# Sensors.net
KiCad netlist of a schematic drawn in Altium Designer
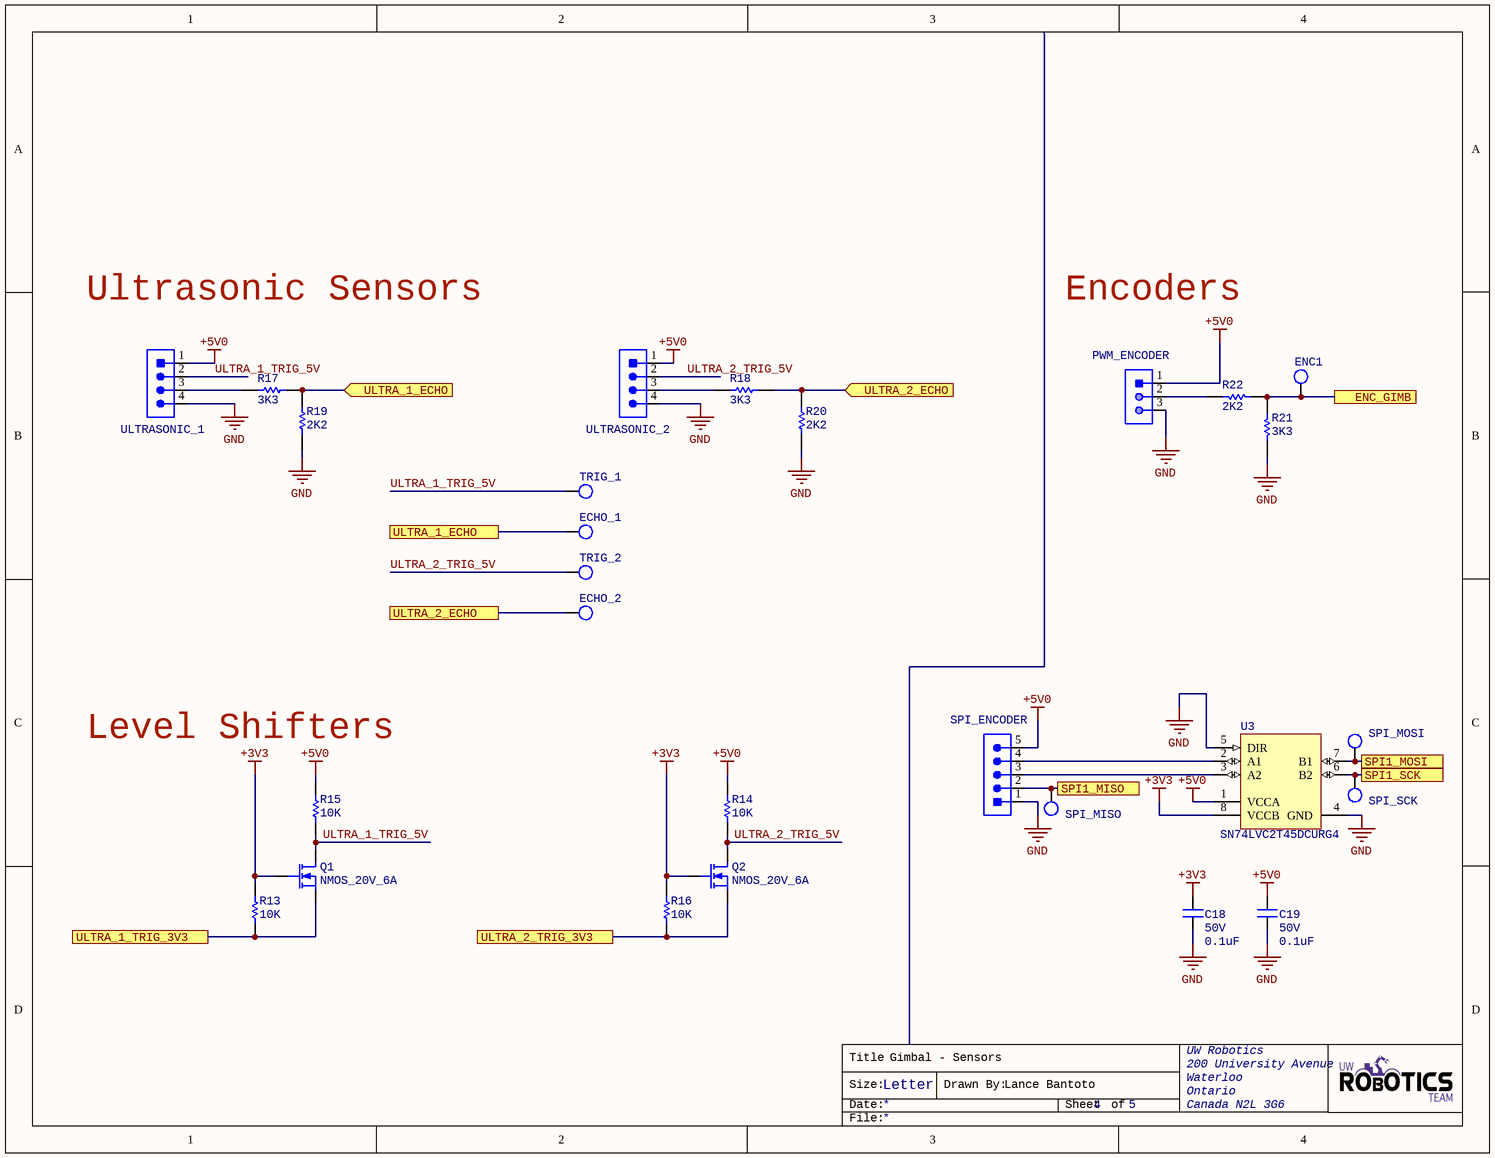
[diagram p0: Sensors.SchDoc]

(export (version "E")
  (design (tool "Eeschema 10.0.6"))
  (components
    (comp (ref "C18")
      (value "0.1uF")
      (footprint "CAPC0603(1608)55_N")
      (description "CAP CER 0.1UF 50V X7R 0603")
      (fields
        (field (name "MPN") "CC0603KRX7R9BB104")
        (field (name "MANUFACTURER") "Yageo")
        (field (name "VOLTAGE RATING") "50V")
      )
      (libsource (lib "UWRT_Schematic_Library_2020") (part "CAP_0.1uF_50V_0603"))
    )
    (comp (ref "C19")
      (value "0.1uF")
      (footprint "CAPC0603(1608)55_N")
      (description "CAP CER 0.1UF 50V X7R 0603")
      (fields
        (field (name "MPN") "CC0603KRX7R9BB104")
        (field (name "MANUFACTURER") "Yageo")
        (field (name "VOLTAGE RATING") "50V")
      )
      (libsource (lib "UWRT_Schematic_Library_2020") (part "CAP_0.1uF_50V_0603"))
    )
    (comp (ref "ECHO_1")
      (value "TESTPOINT_LOOP")
      (footprint "TESTPOINT_LOOP")
      (description "Loop testpoint through-hole pad")
      (fields (field (name "MANUFACTURER") "Keystone Electronics"))
      (libsource (lib "UWRT_Schematic_Library_2020") (part "TESTPOINT_LOOP"))
    )
    (comp (ref "ECHO_2")
      (value "TESTPOINT_LOOP")
      (footprint "TESTPOINT_LOOP")
      (description "Loop testpoint through-hole pad")
      (fields (field (name "MANUFACTURER") "Keystone Electronics"))
      (libsource (lib "UWRT_Schematic_Library_2020") (part "TESTPOINT_LOOP"))
    )
    (comp (ref "ENC1")
      (value "TESTPOINT_LOOP")
      (footprint "TESTPOINT_LOOP")
      (description "Loop testpoint through-hole pad")
      (fields (field (name "MANUFACTURER") "Keystone Electronics"))
      (libsource (lib "UWRT_Schematic_Library_2020") (part "TESTPOINT_LOOP"))
    )
    (comp (ref "PWM_ENCODER")
      (value "CON_3M_SM4")
      (footprint "JST-B3B-SM4-TB")
      (fields
        (field (name "MANUFACTURER") "JST")
        (field (name "MANUFACTURER PART NUMBER") "B3B-PH-SM4-TB(LF)(SN)")
      )
      (libsource (lib "UWRT_Schematic_Library_2020") (part "CON_3M_SM4"))
    )
    (comp (ref "Q1")
      (value "NMOS_20V_6A")
      (footprint "NMOS_SOT23-3")
      (description "MOSFET N-CH 20V 6A SOT23")
      (fields (field (name "MPN") "AO3420") (field (name "MANUFACTURER") "Alpha & Omega"))
      (libsource (lib "UWRT_Schematic_Library_2020") (part "NMOS_20V_6A"))
    )
    (comp (ref "Q2")
      (value "NMOS_20V_6A")
      (footprint "NMOS_SOT23-3")
      (description "MOSFET N-CH 20V 6A SOT23")
      (fields (field (name "MPN") "AO3420") (field (name "MANUFACTURER") "Alpha & Omega"))
      (libsource (lib "UWRT_Schematic_Library_2020") (part "NMOS_20V_6A"))
    )
    (comp (ref "R13")
      (value "10K")
      (footprint "RESC0603(1608)_N")
      (description "RES SMD 10K OHM 5% 1/10W 0603")
      (fields (field (name "MANUFACTURER") "Yageo") (field (name "MPN") "RC0603JR-0710KL"))
      (libsource (lib "UWRT_Schematic_Library_2020") (part "RES_10K_0603"))
    )
    (comp (ref "R14")
      (value "10K")
      (footprint "RESC0603(1608)_N")
      (description "RES SMD 10K OHM 5% 1/10W 0603")
      (fields (field (name "MANUFACTURER") "Yageo") (field (name "MPN") "RC0603JR-0710KL"))
      (libsource (lib "UWRT_Schematic_Library_2020") (part "RES_10K_0603"))
    )
    (comp (ref "R15")
      (value "10K")
      (footprint "RESC0603(1608)_N")
      (description "RES SMD 10K OHM 5% 1/10W 0603")
      (fields (field (name "MANUFACTURER") "Yageo") (field (name "MPN") "RC0603JR-0710KL"))
      (libsource (lib "UWRT_Schematic_Library_2020") (part "RES_10K_0603"))
    )
    (comp (ref "R16")
      (value "10K")
      (footprint "RESC0603(1608)_N")
      (description "RES SMD 10K OHM 5% 1/10W 0603")
      (fields (field (name "MANUFACTURER") "Yageo") (field (name "MPN") "RC0603JR-0710KL"))
      (libsource (lib "UWRT_Schematic_Library_2020") (part "RES_10K_0603"))
    )
    (comp (ref "R17")
      (value "3K3")
      (footprint "RESC0603(1608)_N")
      (description "RES SMD 3.3K OHM 5% 1/10W 0603")
      (fields (field (name "MANUFACTURER") "Yageo") (field (name "TOLERANCE") "5%"))
      (libsource (lib "UWRT_Schematic_Library_2020") (part "RES_3K3_0603"))
    )
    (comp (ref "R18")
      (value "3K3")
      (footprint "RESC0603(1608)_N")
      (description "RES SMD 3.3K OHM 5% 1/10W 0603")
      (fields (field (name "MANUFACTURER") "Yageo") (field (name "TOLERANCE") "5%"))
      (libsource (lib "UWRT_Schematic_Library_2020") (part "RES_3K3_0603"))
    )
    (comp (ref "R19")
      (value "2K2")
      (footprint "RESC0603(1608)_N")
      (description "RES SMD 2.2K OHM 1% 1/10W 0603")
      (fields (field (name "MANUFACTURER") "Yageo") (field (name "TOLERANCE") "1%"))
      (libsource (lib "UWRT_Schematic_Library_2020") (part "RES_2K2_0603"))
    )
    (comp (ref "R20")
      (value "2K2")
      (footprint "RESC0603(1608)_N")
      (description "RES SMD 2.2K OHM 1% 1/10W 0603")
      (fields (field (name "MANUFACTURER") "Yageo") (field (name "TOLERANCE") "1%"))
      (libsource (lib "UWRT_Schematic_Library_2020") (part "RES_2K2_0603"))
    )
    (comp (ref "R21")
      (value "3K3")
      (footprint "RESC0603(1608)_N")
      (description "RES SMD 3.3K OHM 5% 1/10W 0603")
      (fields (field (name "MANUFACTURER") "Yageo") (field (name "TOLERANCE") "5%"))
      (libsource (lib "UWRT_Schematic_Library_2020") (part "RES_3K3_0603"))
    )
    (comp (ref "R22")
      (value "2K2")
      (footprint "RESC0603(1608)_N")
      (description "RES SMD 2.2K OHM 1% 1/10W 0603")
      (fields (field (name "MANUFACTURER") "Yageo") (field (name "TOLERANCE") "1%"))
      (libsource (lib "UWRT_Schematic_Library_2020") (part "RES_2K2_0603"))
    )
    (comp (ref "SPI_ENCODER")
      (value "CON_5M_SM4")
      (footprint "JST-B5B-SM4-TB")
      (fields
        (field (name "MANUFACTURER") "JST")
        (field (name "MANUFACTURER PART NUMBER") "B5B-PH-SM4-TB(LF)(SN)")
      )
      (libsource (lib "UWRT_Schematic_Library_2020") (part "CON_5M_SM4"))
    )
    (comp (ref "SPI_MISO")
      (value "TESTPOINT_LOOP")
      (footprint "TESTPOINT_LOOP")
      (description "Loop testpoint through-hole pad")
      (fields (field (name "MANUFACTURER") "Keystone Electronics"))
      (libsource (lib "UWRT_Schematic_Library_2020") (part "TESTPOINT_LOOP"))
    )
    (comp (ref "SPI_MOSI")
      (value "TESTPOINT_LOOP")
      (footprint "TESTPOINT_LOOP")
      (description "Loop testpoint through-hole pad")
      (fields (field (name "MANUFACTURER") "Keystone Electronics"))
      (libsource (lib "UWRT_Schematic_Library_2020") (part "TESTPOINT_LOOP"))
    )
    (comp (ref "SPI_SCK")
      (value "TESTPOINT_LOOP")
      (footprint "TESTPOINT_LOOP")
      (description "Loop testpoint through-hole pad")
      (fields (field (name "MANUFACTURER") "Keystone Electronics"))
      (libsource (lib "UWRT_Schematic_Library_2020") (part "TESTPOINT_LOOP"))
    )
    (comp (ref "TRIG_1")
      (value "TESTPOINT_LOOP")
      (footprint "TESTPOINT_LOOP")
      (description "Loop testpoint through-hole pad")
      (fields (field (name "MANUFACTURER") "Keystone Electronics"))
      (libsource (lib "UWRT_Schematic_Library_2020") (part "TESTPOINT_LOOP"))
    )
    (comp (ref "TRIG_2")
      (value "TESTPOINT_LOOP")
      (footprint "TESTPOINT_LOOP")
      (description "Loop testpoint through-hole pad")
      (fields (field (name "MANUFACTURER") "Keystone Electronics"))
      (libsource (lib "UWRT_Schematic_Library_2020") (part "TESTPOINT_LOOP"))
    )
    (comp (ref "U3")
      (value "SN74LVC2T45DCURG4")
      (footprint "DCU0008A_L")
      (fields
        (field (name "MANUFACTURER") "Texas Instruments")
        (field (name "GENERIC PART NUMBER") "SN74LVC2T45")
      )
      (libsource (lib "Altium Content Vault") (part "TI-SN74XVC2T45-8"))
    )
    (comp (ref "ULTRASONIC_1")
      (value "CON_4M_SM4")
      (footprint "JST-B4B-SM4-TB")
      (fields
        (field (name "MANUFACTURER") "JST")
        (field (name "MANUFACTURER PART NUMBER") "B4B-PH-SM4-TB(LF)(SN)")
      )
      (libsource (lib "UWRT_Schematic_Library_2020") (part "CON_4M_SM4"))
    )
    (comp (ref "ULTRASONIC_2")
      (value "CON_4M_SM4")
      (footprint "JST-B4B-SM4-TB")
      (fields
        (field (name "MANUFACTURER") "JST")
        (field (name "MANUFACTURER PART NUMBER") "B4B-PH-SM4-TB(LF)(SN)")
      )
      (libsource (lib "UWRT_Schematic_Library_2020") (part "CON_4M_SM4"))
    )
  )
  (nets
    (net (code "1") (name "+3V3") (class "Default")
      (node (ref "C18") (pin "2") (pinfunction "2_2") (pintype "passive"))
      (node (ref "Q1") (pin "1") (pinfunction "G_1") (pintype "passive"))
      (node (ref "Q2") (pin "1") (pinfunction "G_1") (pintype "passive"))
      (node (ref "R13") (pin "1") (pinfunction "1_1") (pintype "passive"))
      (node (ref "R16") (pin "1") (pinfunction "1_1") (pintype "passive"))
      (node (ref "U3") (pin "8") (pinfunction "VCCB_8") (pintype "power_in"))
    )
    (net (code "2") (name "+5V0") (class "Default")
      (node (ref "C19") (pin "2") (pinfunction "2_2") (pintype "passive"))
      (node (ref "PWM_ENCODER") (pin "1") (pinfunction "1_1") (pintype "passive"))
      (node (ref "R14") (pin "2") (pinfunction "2_2") (pintype "passive"))
      (node (ref "R15") (pin "2") (pinfunction "2_2") (pintype "passive"))
      (node (ref "SPI_ENCODER") (pin "5") (pinfunction "5_5") (pintype "passive"))
      (node (ref "U3") (pin "1") (pinfunction "VCCA_1") (pintype "power_in"))
      (node (ref "ULTRASONIC_1") (pin "1") (pinfunction "1_1") (pintype "passive"))
      (node (ref "ULTRASONIC_2") (pin "1") (pinfunction "1_1") (pintype "passive"))
    )
    (net (code "3") (name "/ENC_GIMB") (class "Default")
      (node (ref "ENC1") (pin "1") (pintype "passive"))
      (node (ref "R21") (pin "1") (pinfunction "1_1") (pintype "passive"))
      (node (ref "R22") (pin "1") (pinfunction "1_1") (pintype "passive"))
    )
    (net (code "4") (name "/SPI1_MISO") (class "Default")
      (node (ref "SPI_ENCODER") (pin "2") (pinfunction "2_2") (pintype "passive"))
      (node (ref "SPI_MISO") (pin "1") (pintype "passive"))
    )
    (net (code "5") (name "/SPI1_MOSI") (class "Default")
      (node (ref "SPI_MOSI") (pin "1") (pintype "passive"))
      (node (ref "U3") (pin "7") (pinfunction "B1_7") (pintype "bidirectional"))
    )
    (net (code "6") (name "/SPI1_SCK") (class "Default")
      (node (ref "SPI_SCK") (pin "1") (pintype "passive"))
      (node (ref "U3") (pin "6") (pinfunction "B2_6") (pintype "bidirectional"))
    )
    (net (code "7") (name "/ULTRA_1_ECHO") (class "Default")
      (node (ref "ECHO_1") (pin "1") (pintype "passive"))
      (node (ref "R17") (pin "1") (pinfunction "1_1") (pintype "passive"))
      (node (ref "R19") (pin "2") (pinfunction "2_2") (pintype "passive"))
    )
    (net (code "8") (name "/ULTRA_1_TRIG_3V3") (class "Default")
      (node (ref "Q1") (pin "2") (pinfunction "S_2") (pintype "passive"))
      (node (ref "R13") (pin "2") (pinfunction "2_2") (pintype "passive"))
    )
    (net (code "9") (name "/ULTRA_1_TRIG_5V") (class "Default")
      (node (ref "Q1") (pin "3") (pinfunction "D_3") (pintype "passive"))
      (node (ref "R15") (pin "1") (pinfunction "1_1") (pintype "passive"))
      (node (ref "TRIG_1") (pin "1") (pintype "passive"))
      (node (ref "ULTRASONIC_1") (pin "2") (pinfunction "2_2") (pintype "passive"))
    )
    (net (code "10") (name "/ULTRA_2_ECHO") (class "Default")
      (node (ref "ECHO_2") (pin "1") (pintype "passive"))
      (node (ref "R18") (pin "1") (pinfunction "1_1") (pintype "passive"))
      (node (ref "R20") (pin "2") (pinfunction "2_2") (pintype "passive"))
    )
    (net (code "11") (name "/ULTRA_2_TRIG_3V3") (class "Default")
      (node (ref "Q2") (pin "2") (pinfunction "S_2") (pintype "passive"))
      (node (ref "R16") (pin "2") (pinfunction "2_2") (pintype "passive"))
    )
    (net (code "12") (name "/ULTRA_2_TRIG_5V") (class "Default")
      (node (ref "Q2") (pin "3") (pinfunction "D_3") (pintype "passive"))
      (node (ref "R14") (pin "1") (pinfunction "1_1") (pintype "passive"))
      (node (ref "TRIG_2") (pin "1") (pintype "passive"))
      (node (ref "ULTRASONIC_2") (pin "2") (pinfunction "2_2") (pintype "passive"))
    )
    (net (code "13") (name "GND") (class "Default")
      (node (ref "C18") (pin "1") (pinfunction "1_1") (pintype "passive"))
      (node (ref "C19") (pin "1") (pinfunction "1_1") (pintype "passive"))
      (node (ref "PWM_ENCODER") (pin "3") (pinfunction "3_3") (pintype "passive"))
      (node (ref "R19") (pin "1") (pinfunction "1_1") (pintype "passive"))
      (node (ref "R20") (pin "1") (pinfunction "1_1") (pintype "passive"))
      (node (ref "R21") (pin "2") (pinfunction "2_2") (pintype "passive"))
      (node (ref "SPI_ENCODER") (pin "1") (pinfunction "1_1") (pintype "passive"))
      (node (ref "U3") (pin "4") (pinfunction "GND_4") (pintype "power_in"))
      (node (ref "U3") (pin "5") (pinfunction "DIR_5") (pintype "input"))
      (node (ref "ULTRASONIC_1") (pin "4") (pinfunction "4_4") (pintype "passive"))
      (node (ref "ULTRASONIC_2") (pin "4") (pinfunction "4_4") (pintype "passive"))
    )
    (net (code "14") (name "Net-(PWM_ENCODER-Pad2)") (class "Default")
      (node (ref "PWM_ENCODER") (pin "2") (pinfunction "2_2") (pintype "passive"))
      (node (ref "R22") (pin "2") (pinfunction "2_2") (pintype "passive"))
    )
    (net (code "15") (name "Net-(R17-Pad2)") (class "Default")
      (node (ref "R17") (pin "2") (pinfunction "2_2") (pintype "passive"))
      (node (ref "ULTRASONIC_1") (pin "3") (pinfunction "3_3") (pintype "passive"))
    )
    (net (code "16") (name "Net-(R18-Pad2)") (class "Default")
      (node (ref "R18") (pin "2") (pinfunction "2_2") (pintype "passive"))
      (node (ref "ULTRASONIC_2") (pin "3") (pinfunction "3_3") (pintype "passive"))
    )
    (net (code "17") (name "Net-(U3-A1)") (class "Default")
      (node (ref "SPI_ENCODER") (pin "4") (pinfunction "4_4") (pintype "passive"))
      (node (ref "U3") (pin "2") (pinfunction "A1_2") (pintype "bidirectional"))
    )
    (net (code "18") (name "Net-(U3-A2)") (class "Default")
      (node (ref "SPI_ENCODER") (pin "3") (pinfunction "3_3") (pintype "passive"))
      (node (ref "U3") (pin "3") (pinfunction "A2_3") (pintype "bidirectional"))
    )
  )
)
